# source_eagle.net
KiCad netlist of a schematic drawn in EAGLE
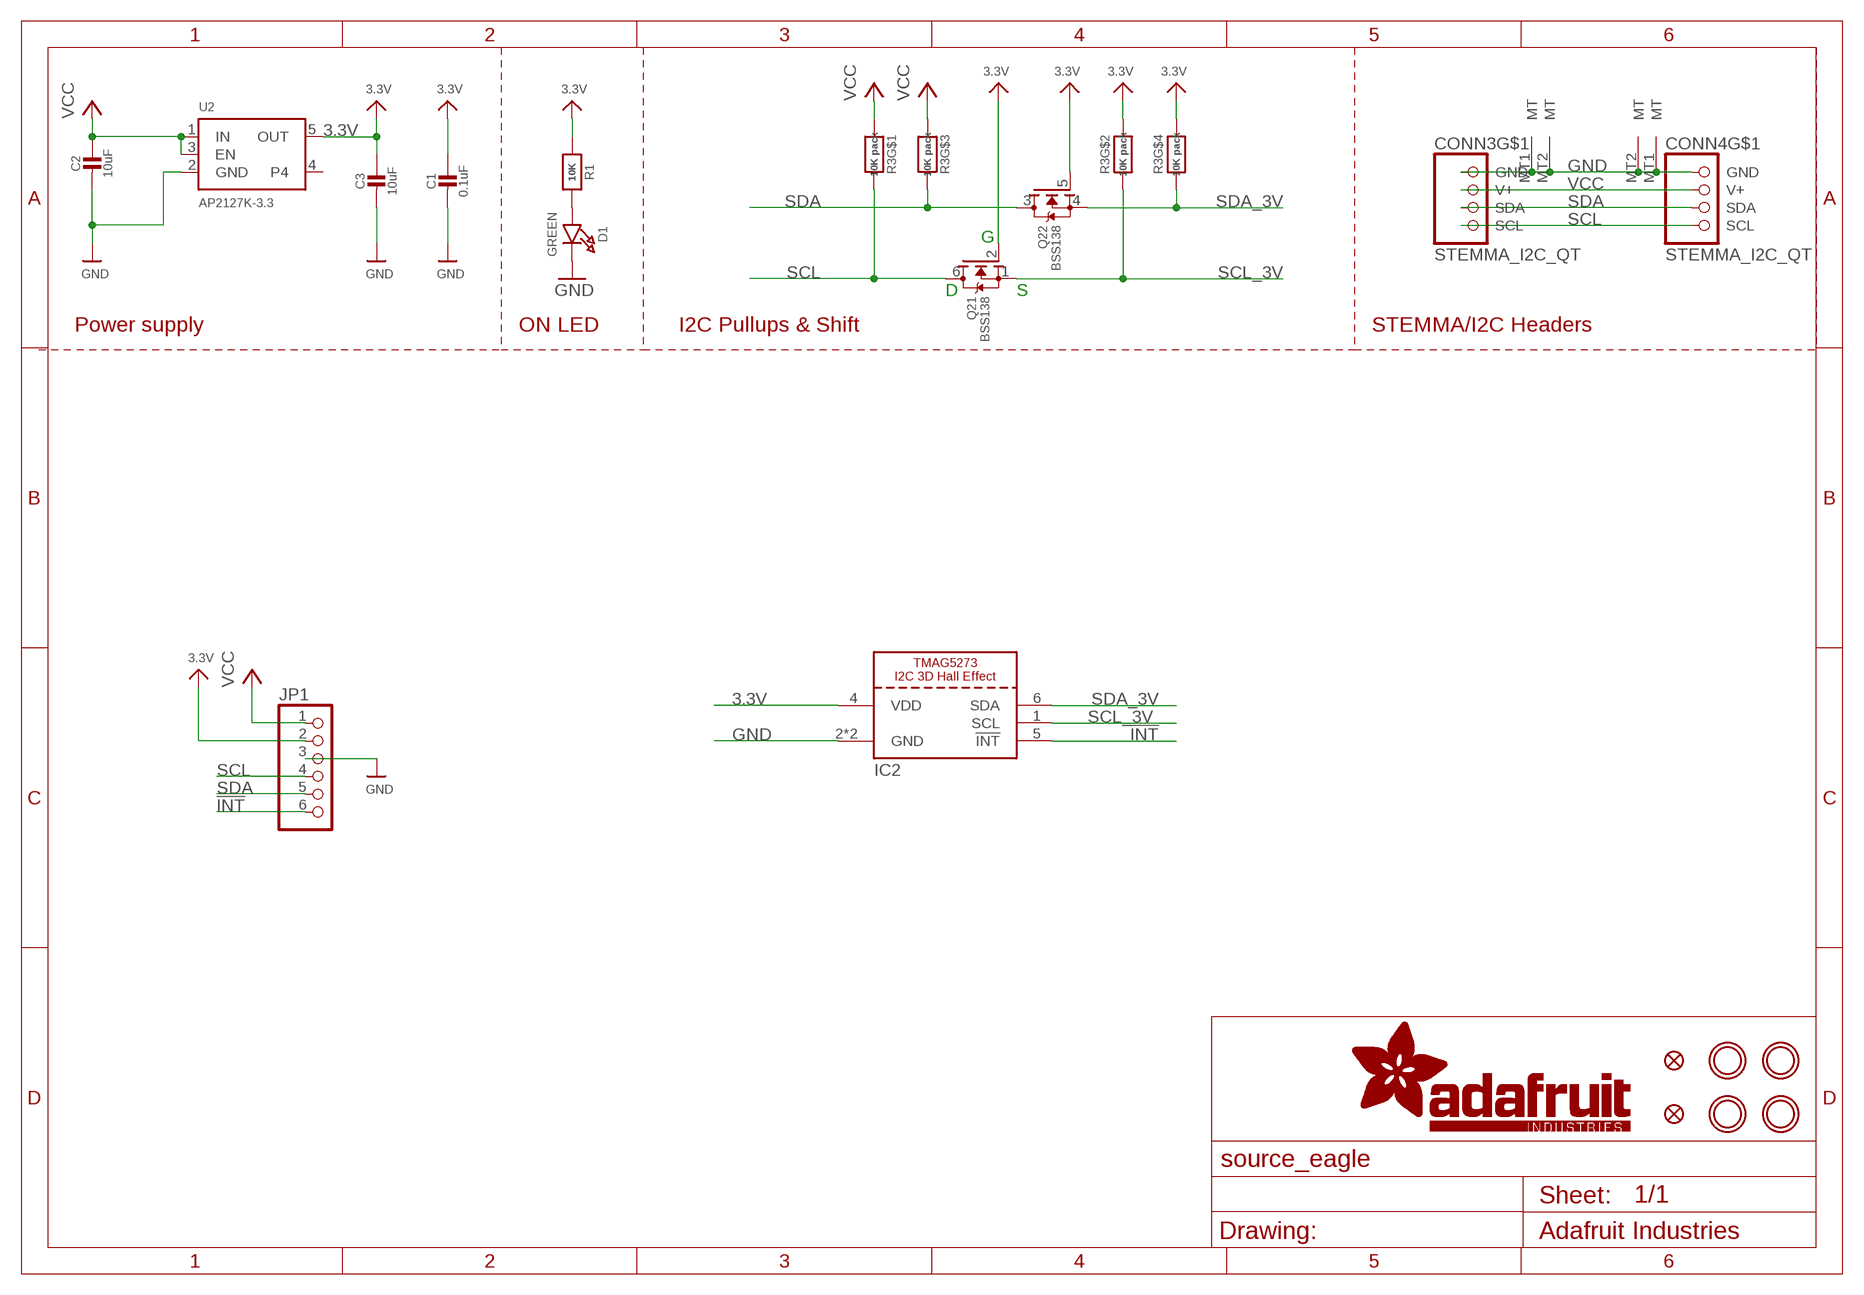
[diagram p0: schematic, sheet 1]

(export (version "E")
  (design (tool "Eeschema 10.0.6"))
  (components
    (comp (ref "C1")
      (value "0.1uF")
      (footprint "eagle-import:0603-NO")
      (libsource (lib "eagle-import") (part "CAP_CERAMIC0603_NO"))
    )
    (comp (ref "C2")
      (value "10uF")
      (footprint "eagle-import:0805-NO")
      (libsource (lib "eagle-import") (part "CAP_CERAMIC0805-NOOUTLINE"))
    )
    (comp (ref "C3")
      (value "10uF")
      (footprint "eagle-import:0805-NO")
      (libsource (lib "eagle-import") (part "CAP_CERAMIC0805-NOOUTLINE"))
    )
    (comp (ref "CONN3")
      (value "STEMMA_I2C_QT")
      (footprint "eagle-import:JST_SH4")
      (libsource (lib "eagle-import") (part "STEMMA_I2C_QT"))
    )
    (comp (ref "CONN4")
      (value "STEMMA_I2C_QT")
      (footprint "eagle-import:JST_SH4")
      (libsource (lib "eagle-import") (part "STEMMA_I2C_QT"))
    )
    (comp (ref "D1")
      (value "GREEN")
      (footprint "eagle-import:CHIPLED_0603_NOOUTLINE")
      (libsource (lib "eagle-import") (part "LED0603_NOOUTLINE"))
    )
    (comp (ref "FID3")
      (value "FIDUCIAL_0.5MM")
      (footprint "eagle-import:FIDUCIAL_0.5MM")
      (libsource (lib "eagle-import") (part "FIDUCIAL_0.5MM"))
    )
    (comp (ref "FID4")
      (value "FIDUCIAL_0.5MM")
      (footprint "eagle-import:FIDUCIAL_0.5MM")
      (libsource (lib "eagle-import") (part "FIDUCIAL_0.5MM"))
    )
    (comp (ref "IC2")
      (value "TMAG5273A1")
      (footprint "eagle-import:SOT23-6")
      (fields (field (name "ROT") "90"))
      (libsource (lib "eagle-import") (part "TMAG5273"))
    )
    (comp (ref "JP1")
      (value "HEADER-1X670MIL")
      (footprint "eagle-import:1X06_ROUND_70")
      (libsource (lib "eagle-import") (part "HEADER-1X670MIL"))
    )
    (comp (ref "Q2")
      (value "BSS138")
      (footprint "eagle-import:SOT363")
      (libsource (lib "eagle-import") (part "MOSFET-N_DUAL"))
    )
    (comp (ref "R1")
      (value "10K")
      (footprint "eagle-import:0603-NO")
      (libsource (lib "eagle-import") (part "RESISTOR_0603_NOOUT"))
    )
    (comp (ref "R3")
      (value "10K pack")
      (footprint "eagle-import:RESPACK_4X0603")
      (libsource (lib "eagle-import") (part "RESISTOR_4PACK"))
    )
    (comp (ref "U$1")
      (value "MOUNTINGHOLE2.5")
      (footprint "eagle-import:MOUNTINGHOLE_2.5_PLATED")
      (libsource (lib "eagle-import") (part "MOUNTINGHOLE2.5"))
    )
    (comp (ref "U$17")
      (value "MOUNTINGHOLE2.5")
      (footprint "eagle-import:MOUNTINGHOLE_2.5_PLATED")
      (libsource (lib "eagle-import") (part "MOUNTINGHOLE2.5"))
    )
    (comp (ref "U$19")
      (value "MOUNTINGHOLE2.5")
      (footprint "eagle-import:MOUNTINGHOLE_2.5_PLATED")
      (libsource (lib "eagle-import") (part "MOUNTINGHOLE2.5"))
    )
    (comp (ref "U$21")
      (value "MOUNTINGHOLE2.5")
      (footprint "eagle-import:MOUNTINGHOLE_2.5_PLATED")
      (libsource (lib "eagle-import") (part "MOUNTINGHOLE2.5"))
    )
    (comp (ref "U2")
      (value "AP2127K-3.3")
      (footprint "eagle-import:SOT23-5")
      (libsource (lib "eagle-import") (part "VREG_SOT23-5"))
    )
  )
  (nets
    (net (code "1") (name "/SCL") (class "Default")
      (node (ref "CONN3") (pin "4") (pinfunction "SCL_4") (pintype "passive"))
      (node (ref "CONN4") (pin "4") (pinfunction "SCL_4") (pintype "passive"))
      (node (ref "JP1") (pin "4") (pinfunction "4_4") (pintype "passive"))
      (node (ref "Q2") (pin "6") (pinfunction "D_6") (pintype "bidirectional"))
      (node (ref "R3") (pin "8") (pinfunction "2_8") (pintype "passive"))
    )
    (net (code "2") (name "/SCL_3V") (class "Default")
      (node (ref "IC2") (pin "1") (pinfunction "SCL_1") (pintype "bidirectional"))
      (node (ref "Q2") (pin "1") (pinfunction "S_1") (pintype "bidirectional"))
      (node (ref "R3") (pin "7") (pinfunction "2_7") (pintype "passive"))
    )
    (net (code "3") (name "/SDA") (class "Default")
      (node (ref "CONN3") (pin "3") (pinfunction "SDA_3") (pintype "passive"))
      (node (ref "CONN4") (pin "3") (pinfunction "SDA_3") (pintype "passive"))
      (node (ref "JP1") (pin "5") (pinfunction "5_5") (pintype "passive"))
      (node (ref "Q2") (pin "3") (pinfunction "D_3") (pintype "bidirectional"))
      (node (ref "R3") (pin "6") (pinfunction "2_6") (pintype "passive"))
    )
    (net (code "4") (name "/SDA_3V") (class "Default")
      (node (ref "IC2") (pin "6") (pinfunction "SDA_6") (pintype "bidirectional"))
      (node (ref "Q2") (pin "4") (pinfunction "S_4") (pintype "bidirectional"))
      (node (ref "R3") (pin "5") (pinfunction "2_5") (pintype "passive"))
    )
    (net (code "5") (name "/~{INT}") (class "Default")
      (node (ref "IC2") (pin "5") (pinfunction "~{INT}_5") (pintype "output"))
      (node (ref "JP1") (pin "6") (pinfunction "6_6") (pintype "passive"))
    )
    (net (code "6") (name "3.3V") (class "Default")
      (node (ref "C1") (pin "1") (pinfunction "1_1") (pintype "passive"))
      (node (ref "C3") (pin "1") (pinfunction "1_1") (pintype "passive"))
      (node (ref "IC2") (pin "4") (pinfunction "VDD_4") (pintype "power_in"))
      (node (ref "JP1") (pin "2") (pinfunction "2_2") (pintype "passive"))
      (node (ref "Q2") (pin "2") (pinfunction "G_2") (pintype "bidirectional"))
      (node (ref "Q2") (pin "5") (pinfunction "G_5") (pintype "bidirectional"))
      (node (ref "R1") (pin "1") (pinfunction "1_1") (pintype "passive"))
      (node (ref "R3") (pin "2") (pinfunction "1_2") (pintype "passive"))
      (node (ref "R3") (pin "4") (pinfunction "1_4") (pintype "passive"))
      (node (ref "U2") (pin "5") (pinfunction "OUT_5") (pintype "power_in"))
    )
    (net (code "7") (name "GND") (class "Default")
      (node (ref "C1") (pin "2") (pinfunction "2_2") (pintype "passive"))
      (node (ref "C2") (pin "2") (pinfunction "2_2") (pintype "passive"))
      (node (ref "C3") (pin "2") (pinfunction "2_2") (pintype "passive"))
      (node (ref "CONN3") (pin "1") (pinfunction "GND_1") (pintype "passive"))
      (node (ref "CONN3") (pin "MT1") (pinfunction "MT_MT1") (pintype "bidirectional"))
      (node (ref "CONN3") (pin "MT2") (pinfunction "MT_MT2") (pintype "bidirectional"))
      (node (ref "CONN4") (pin "1") (pinfunction "GND_1") (pintype "passive"))
      (node (ref "CONN4") (pin "MT1") (pinfunction "MT_MT1") (pintype "bidirectional"))
      (node (ref "CONN4") (pin "MT2") (pinfunction "MT_MT2") (pintype "bidirectional"))
      (node (ref "D1") (pin "C") (pinfunction "C_C") (pintype "passive"))
      (node (ref "IC2") (pin "2") (pinfunction "GND_2") (pintype "power_in"))
      (node (ref "IC2") (pin "3") (pinfunction "GND_3") (pintype "power_in"))
      (node (ref "JP1") (pin "3") (pinfunction "3_3") (pintype "passive"))
      (node (ref "U2") (pin "2") (pinfunction "GND_2") (pintype "power_in"))
    )
    (net (code "8") (name "Net-(D1-PadA)") (class "Default")
      (node (ref "D1") (pin "A") (pinfunction "A_A") (pintype "passive"))
      (node (ref "R1") (pin "2") (pinfunction "2_2") (pintype "passive"))
    )
    (net (code "9") (name "VCC") (class "Default")
      (node (ref "C2") (pin "1") (pinfunction "1_1") (pintype "passive"))
      (node (ref "CONN3") (pin "2") (pinfunction "V+_2") (pintype "passive"))
      (node (ref "CONN4") (pin "2") (pinfunction "V+_2") (pintype "passive"))
      (node (ref "JP1") (pin "1") (pinfunction "1_1") (pintype "passive"))
      (node (ref "R3") (pin "1") (pinfunction "1_1") (pintype "passive"))
      (node (ref "R3") (pin "3") (pinfunction "1_3") (pintype "passive"))
      (node (ref "U2") (pin "1") (pinfunction "IN_1") (pintype "power_in"))
      (node (ref "U2") (pin "3") (pinfunction "EN_3") (pintype "input"))
    )
    (net (code "10") (name "unconnected-(U2-P4-Pad4)") (class "Default")
      (node (ref "U2") (pin "4") (pinfunction "P4_4") (pintype "bidirectional"))
    )
  )
)
